# ESP_SCHEMATIC.net
KiCad netlist of a schematic drawn in Altium Designer
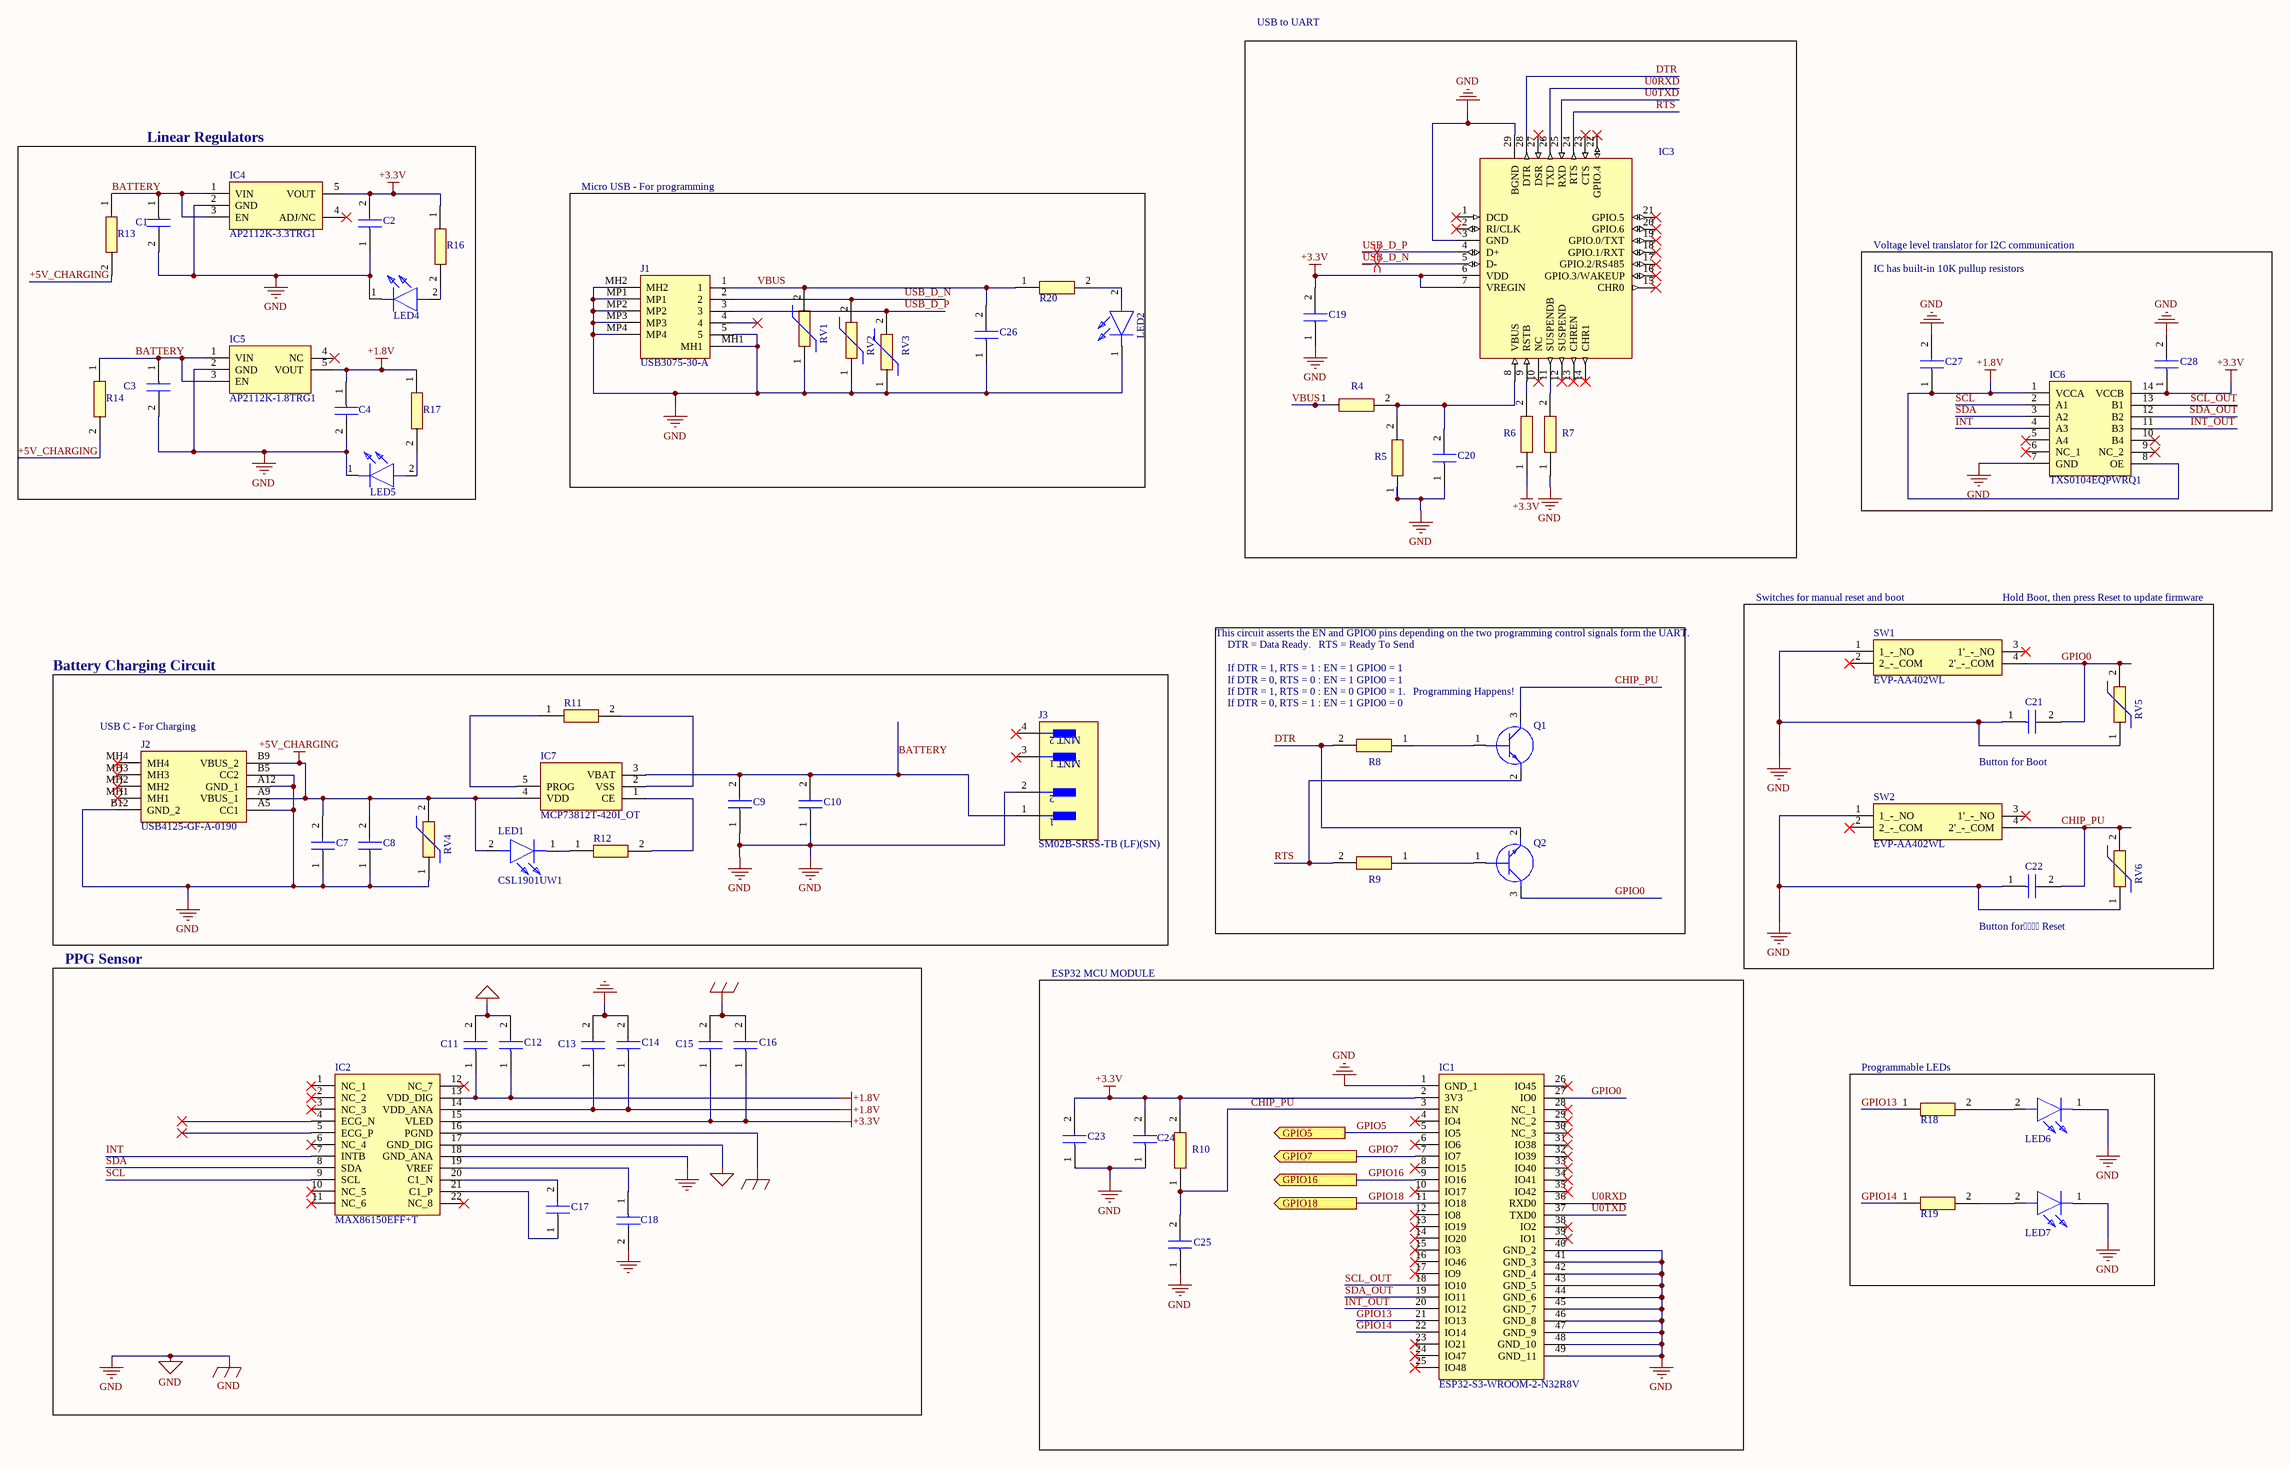
[diagram p0: ESP_SCHEMATIC.SchDoc]

(export (version "E")
  (design (tool "Eeschema 10.0.6"))
  (components
    (comp (ref "C1")
      (value "CGA3E1X7R1C105K080AC")
      (footprint "SamacSys:CAPC1608X90N")
      (description "Capacitor")
      (fields (field (name "MOUSER PART NUMBER") "810-CGA3E1X7R1C105AC"))
      (libsource (lib "*") (part "CGA3E1X7R1C105K080AC"))
    )
    (comp (ref "C2")
      (value "GRM188R71A225KE15J")
      (footprint "SamacSys:CAPC1608X90N")
      (description "Capacitor")
      (fields (field (name "MOUSER PART NUMBER") "81-GRM188R71A225KE5J"))
      (libsource (lib "*") (part "GRM188R71A225KE15J"))
    )
    (comp (ref "C3")
      (value "CGA3E1X7R1C105K080AC")
      (footprint "SamacSys:CAPC1608X90N")
      (description "Capacitor")
      (fields (field (name "MOUSER PART NUMBER") "810-CGA3E1X7R1C105AC"))
      (libsource (lib "*") (part "CGA3E1X7R1C105K080AC"))
    )
    (comp (ref "C4")
      (value "CGA3E1X7R1C105K080AC")
      (footprint "SamacSys:CAPC1608X90N")
      (description "Capacitor")
      (fields (field (name "MOUSER PART NUMBER") "810-CGA3E1X7R1C105AC"))
      (libsource (lib "*") (part "CGA3E1X7R1C105K080AC"))
    )
    (comp (ref "C7")
      (value "C0603C104K8RAC")
      (footprint "SamacSys:CAPC1608X95N")
      (description "Capacitor")
      (fields (field (name "MOUSER PART NUMBER") "80-C0603C104K8RAC"))
      (libsource (lib "*") (part "C0603C104K8RAC"))
    )
    (comp (ref "C8")
      (value "GRM188R61E106KA73J")
      (footprint "SamacSys:CAPC1608X90N")
      (description "Capacitor")
      (fields (field (name "MOUSER PART NUMBER") "81-GRM188R61E106KA3J"))
      (libsource (lib "*") (part "GRM188R61E106KA73J"))
    )
    (comp (ref "C9")
      (value "C0603C104K8RAC")
      (footprint "SamacSys:CAPC1608X95N")
      (description "Capacitor")
      (fields (field (name "MOUSER PART NUMBER") "80-C0603C104K8RAC"))
      (libsource (lib "*") (part "C0603C104K8RAC"))
    )
    (comp (ref "C10")
      (value "GRM188R61E106KA73J")
      (footprint "SamacSys:CAPC1608X90N")
      (description "Capacitor")
      (fields (field (name "MOUSER PART NUMBER") "81-GRM188R61E106KA3J"))
      (libsource (lib "*") (part "GRM188R61E106KA73J"))
    )
    (comp (ref "C11")
      (value "C1608X5R1E475K080AC")
      (footprint "SamacSys:CAPC1608X80N")
      (description "Capacitor")
      (fields (field (name "MOUSER PART NUMBER") "810-C1608X5R1E475K"))
      (libsource (lib "*") (part "C1608X5R1E475K080AC"))
    )
    (comp (ref "C12")
      (value "C0603C104K8RAC")
      (footprint "SamacSys:CAPC1608X95N")
      (description "Capacitor")
      (fields (field (name "MOUSER PART NUMBER") "80-C0603C104K8RAC"))
      (libsource (lib "*") (part "C0603C104K8RAC"))
    )
    (comp (ref "C13")
      (value "C1608X5R1E475K080AC")
      (footprint "SamacSys:CAPC1608X80N")
      (description "Capacitor")
      (fields (field (name "MOUSER PART NUMBER") "810-C1608X5R1E475K"))
      (libsource (lib "*") (part "C1608X5R1E475K080AC"))
    )
    (comp (ref "C14")
      (value "C0603C104K8RAC")
      (footprint "SamacSys:CAPC1608X95N")
      (description "Capacitor")
      (fields (field (name "MOUSER PART NUMBER") "80-C0603C104K8RAC"))
      (libsource (lib "*") (part "C0603C104K8RAC"))
    )
    (comp (ref "C15")
      (value "GRM188R61E106KA73J")
      (footprint "SamacSys:CAPC1608X90N")
      (description "Capacitor")
      (fields (field (name "MOUSER PART NUMBER") "81-GRM188R61E106KA3J"))
      (libsource (lib "*") (part "GRM188R61E106KA73J"))
    )
    (comp (ref "C16")
      (value "C0603C104K8RAC")
      (footprint "SamacSys:CAPC1608X95N")
      (description "Capacitor")
      (fields (field (name "MOUSER PART NUMBER") "80-C0603C104K8RAC"))
      (libsource (lib "*") (part "C0603C104K8RAC"))
    )
    (comp (ref "C17")
      (value "CGA3E1X7R1C105K080AC")
      (footprint "SamacSys:CAPC1608X90N")
      (description "Capacitor")
      (fields (field (name "MOUSER PART NUMBER") "810-CGA3E1X7R1C105AC"))
      (libsource (lib "*") (part "CGA3E1X7R1C105K080AC"))
    )
    (comp (ref "C18")
      (value "CGA3E1X7R1C105K080AC")
      (footprint "SamacSys:CAPC1608X90N")
      (description "Capacitor")
      (fields (field (name "MOUSER PART NUMBER") "810-CGA3E1X7R1C105AC"))
      (libsource (lib "*") (part "CGA3E1X7R1C105K080AC"))
    )
    (comp (ref "C19")
      (value "GRM188R61E106MA73J")
      (footprint "SamacSys:CAPC1608X90N")
      (description "Capacitor")
      (fields (field (name "MOUSER PART NUMBER") "81-GRM188R61E106MA3J"))
      (libsource (lib "*") (part "GRM188R61E106MA73J"))
    )
    (comp (ref "C20")
      (value "GRT188R61C105KE13D")
      (footprint "SamacSys:CAPC1608X90N")
      (description "Capacitor")
      (fields (field (name "MOUSER PART NUMBER") "81-GRT188R61C105KE3D"))
      (libsource (lib "*") (part "GRT188R61C105KE13D"))
    )
    (comp (ref "C21")
      (value "C0603C104K5RAC3121")
      (footprint "SamacSys:CAPC1608X95N")
      (description "Capacitor")
      (fields (field (name "MOUSER PART NUMBER") "80-C603C104K5RAC3121"))
      (libsource (lib "*") (part "C0603C104K5RAC3121"))
    )
    (comp (ref "C22")
      (value "C0603C104K5RAC3121")
      (footprint "SamacSys:CAPC1608X95N")
      (description "Capacitor")
      (fields (field (name "MOUSER PART NUMBER") "80-C603C104K5RAC3121"))
      (libsource (lib "*") (part "C0603C104K5RAC3121"))
    )
    (comp (ref "C23")
      (value "C0603C104K8RAC")
      (footprint "SamacSys:CAPC1608X95N")
      (description "Capacitor")
      (fields (field (name "MOUSER PART NUMBER") "80-C0603C104K8RAC"))
      (libsource (lib "*") (part "C0603C104K8RAC"))
    )
    (comp (ref "C24")
      (value "GRM188R61E106KA73J")
      (footprint "SamacSys:CAPC1608X90N")
      (description "Capacitor")
      (fields (field (name "MOUSER PART NUMBER") "81-GRM188R61E106KA3J"))
      (libsource (lib "*") (part "GRM188R61E106KA73J"))
    )
    (comp (ref "C25")
      (value "C0603C105K4RACTU")
      (footprint "SamacSys:C0603")
      (description "Capacitor")
      (fields (field (name "MOUSER PART NUMBER") "80-C0603C105K4R"))
      (libsource (lib "*") (part "C0603C105K4RACTU"))
    )
    (comp (ref "C26")
      (value "GRM188R61E106MA73J")
      (footprint "SamacSys:CAPC1608X90N")
      (description "Capacitor")
      (fields (field (name "MOUSER PART NUMBER") "81-GRM188R61E106MA3J"))
      (libsource (lib "*") (part "GRM188R61E106MA73J"))
    )
    (comp (ref "C27")
      (value "C0603C104K8RAC")
      (footprint "SamacSys:CAPC1608X95N")
      (description "Capacitor")
      (fields (field (name "MOUSER PART NUMBER") "80-C0603C104K8RAC"))
      (libsource (lib "*") (part "C0603C104K8RAC"))
    )
    (comp (ref "C28")
      (value "C0603C104K8RAC")
      (footprint "SamacSys:CAPC1608X95N")
      (description "Capacitor")
      (fields (field (name "MOUSER PART NUMBER") "80-C0603C104K8RAC"))
      (libsource (lib "*") (part "C0603C104K8RAC"))
    )
    (comp (ref "IC1")
      (value "ESP32-S3-WROOM-2-N32R8V")
      (footprint "SamacSys:ESP32S3WROOM2N32R8V")
      (description "Integrated Circuit")
      (fields (field (name "MOUSER PART NUMBER") "356-ESP3S3WRM2N32R8V"))
      (libsource (lib "*") (part "ESP32-S3-WROOM-2-N32R8V"))
    )
    (comp (ref "IC2")
      (value "MAX86150EFF+T")
      (footprint "SamacSys:MAX86150EFFT")
      (description "Integrated Circuit")
      (fields (field (name "MOUSER PART NUMBER") "700-MAX86150EFF+T"))
      (libsource (lib "SamacSys") (part "MAX86150EFF+T"))
    )
    (comp (ref "IC3")
      (value "CP2102N-A02-GQFN28")
      (footprint "SamacSys:QFN50P500X500X80-29N-D")
      (description "Integrated Circuit")
      (fields (field (name "MOUSER PART NUMBER") "634-CP2102NA02GQFN28"))
      (libsource (lib "*") (part "CP2102N-A02-GQFN28"))
    )
    (comp (ref "IC4")
      (value "AP2112K-3.3TRG1")
      (footprint "SamacSys:SOT95P282X130-5N")
      (description "Integrated Circuit")
      (fields (field (name "MOUSER PART NUMBER") "621-AP2112K-3.3TRG1"))
      (libsource (lib "*") (part "AP2112K-3.3TRG1"))
    )
    (comp (ref "IC5")
      (value "AP2112K-1.8TRG1")
      (footprint "SamacSys:SOT95P285X140-5N")
      (description "Integrated Circuit")
      (fields (field (name "MOUSER PART NUMBER") "621-AP2112K-1.8TRG1"))
      (libsource (lib "*") (part "AP2112K-1.8TRG1"))
    )
    (comp (ref "IC6")
      (value "TXS0104EQPWRQ1")
      (footprint "SamacSys:SOP65P640X120-14N")
      (description "Integrated Circuit")
      (fields (field (name "MOUSER PART NUMBER") "595-TXS0104EQPWRQ1"))
      (libsource (lib "*") (part "TXS0104EQPWRQ1"))
    )
    (comp (ref "IC7")
      (value "MCP73812T-420I_OT")
      (footprint "SamacSys:SOT95P270X145-5N")
      (description "Integrated Circuit")
      (fields
        (field (name "MANUFACTURER_PART_NUMBER") "MCP73812T-420I/OT")
        (field (name "MOUSER PART NUMBER") "579-MCP73812T-420IOT")
      )
      (libsource (lib "*") (part "MCP73812T-420I_OT"))
    )
    (comp (ref "J1")
      (value "USB3075-30-A")
      (footprint "SamacSys:USB307530A")
      (description "Connector")
      (fields (field (name "MOUSER PART NUMBER") "640-USB3075-30-A"))
      (libsource (lib "*") (part "USB3075-30-A"))
    )
    (comp (ref "J2")
      (value "USB4125-GF-A-0190")
      (footprint "SamacSys:USB4125GFA0190")
      (description "Connector")
      (fields (field (name "MOUSER PART NUMBER") "640-USB4125-GF-A-190"))
      (libsource (lib "*") (part "USB4125-GF-A-0190"))
    )
    (comp (ref "J3")
      (value "SM02B-SRSS-TB (LF)(SN)")
      (footprint "FP-SM02B-SRSS-TB_LF_SN-MFG")
      (description "CONN HEADER SMD R/A 2POS 1MM")
      (libsource (lib "Altium Content Vault") (part "029478cb6d4f2fad0cd2a245525ee6d"))
    )
    (comp (ref "LED1")
      (value "CSL1901UW1")
      (footprint "SamacSys:CSL1901UW1")
      (description "LED")
      (fields (field (name "MOUSER PART NUMBER") "755-CSL1901UW1"))
      (libsource (lib "*") (part "CSL1901UW1"))
    )
    (comp (ref "LED2")
      (value "SMLD12BN1WT86")
      (footprint "SamacSys:LEDM168X65N")
      (description "LED")
      (fields (field (name "MOUSER PART NUMBER") "755-SMLD12BN1WT86"))
      (libsource (lib "*") (part "SMLD12BN1WT86"))
    )
    (comp (ref "LED4")
      (value "CSL1901YW1")
      (footprint "SamacSys:CSL1901YW1")
      (description "LED")
      (fields (field (name "MOUSER PART NUMBER") "755-CSL1901YW1"))
      (libsource (lib "*") (part "CSL1901YW1"))
    )
    (comp (ref "LED5")
      (value "CSL1901YW1")
      (footprint "SamacSys:CSL1901YW1")
      (description "LED")
      (fields (field (name "MOUSER PART NUMBER") "755-CSL1901YW1"))
      (libsource (lib "*") (part "CSL1901YW1"))
    )
    (comp (ref "LED6")
      (value "CSL1901YW1")
      (footprint "SamacSys:CSL1901YW1")
      (description "LED")
      (fields (field (name "MOUSER PART NUMBER") "755-CSL1901YW1"))
      (libsource (lib "*") (part "CSL1901YW1"))
    )
    (comp (ref "LED7")
      (value "CSL1901YW1")
      (footprint "SamacSys:CSL1901YW1")
      (description "LED")
      (fields (field (name "MOUSER PART NUMBER") "755-CSL1901YW1"))
      (libsource (lib "*") (part "CSL1901YW1"))
    )
    (comp (ref "Q1")
      (value "KSC3265YMTF")
      (footprint "SamacSys:SOT96P237X111-3N")
      (description "Transistor BJT NPN")
      (fields (field (name "MOUSER PART NUMBER") "512-KSC3265YMTF"))
      (libsource (lib "*") (part "KSC3265YMTF"))
    )
    (comp (ref "Q2")
      (value "KSC3265YMTF")
      (footprint "SamacSys:SOT96P237X111-3N")
      (description "Transistor BJT NPN")
      (fields (field (name "MOUSER PART NUMBER") "512-KSC3265YMTF"))
      (libsource (lib "*") (part "KSC3265YMTF"))
    )
    (comp (ref "R4")
      (value "ERJUP3F2212V")
      (footprint "SamacSys:ERJUP3")
      (description "Resistor")
      (libsource (lib "*") (part "ERJUP3F2212V"))
    )
    (comp (ref "R5")
      (value "ERJUP3F4752V")
      (footprint "SamacSys:ERJUP3")
      (description "Resistor")
      (libsource (lib "*") (part "ERJUP3F4752V"))
    )
    (comp (ref "R6")
      (value "ERJUP3F1001V")
      (footprint "SamacSys:ERJUP3")
      (description "Resistor")
      (libsource (lib "") (part "ERJUP3F1001V_1"))
    )
    (comp (ref "R7")
      (value "ERJ-UP3J103V")
      (footprint "SamacSys:ERJUP3")
      (description "Resistor")
      (fields (field (name "MOUSER PART NUMBER") "667-ERJ-UP3J103V"))
      (libsource (lib "*") (part "ERJ-UP3J103V"))
    )
    (comp (ref "R8")
      (value "ERJ-UP3J103V")
      (footprint "SamacSys:ERJUP3")
      (description "Resistor")
      (fields (field (name "MOUSER PART NUMBER") "667-ERJ-UP3J103V"))
      (libsource (lib "") (part "ERJ-UP3J103V_1"))
    )
    (comp (ref "R9")
      (value "ERJ-UP3J103V")
      (footprint "SamacSys:ERJUP3")
      (description "Resistor")
      (fields (field (name "MOUSER PART NUMBER") "667-ERJ-UP3J103V"))
      (libsource (lib "") (part "ERJ-UP3J103V_1"))
    )
    (comp (ref "R10")
      (value "ERJ-UP3J103V")
      (footprint "SamacSys:ERJUP3")
      (description "Resistor")
      (fields (field (name "MOUSER PART NUMBER") "667-ERJ-UP3J103V"))
      (libsource (lib "*") (part "ERJ-UP3J103V"))
    )
    (comp (ref "R11")
      (value "ERJUP3F2001V")
      (footprint "SamacSys:ERJUP3")
      (description "Resistor")
      (libsource (lib "*") (part "ERJUP3F2001V"))
    )
    (comp (ref "R12")
      (value "ERJUP3F1001V")
      (footprint "SamacSys:ERJUP3")
      (description "Resistor")
      (libsource (lib "*") (part "ERJUP3F1001V"))
    )
    (comp (ref "R13")
      (value "ERA-3AEB101V")
      (footprint "SamacSys:ERA3AEB101V")
      (description "Resistor")
      (fields (field (name "MOUSER PART NUMBER") "667-ERA-3AEB101V"))
      (libsource (lib "*") (part "ERA-3AEB101V"))
    )
    (comp (ref "R14")
      (value "ERA-3AEB101V")
      (footprint "SamacSys:ERA3AEB101V")
      (description "Resistor")
      (fields (field (name "MOUSER PART NUMBER") "667-ERA-3AEB101V"))
      (libsource (lib "*") (part "ERA-3AEB101V"))
    )
    (comp (ref "R16")
      (value "RT0603BRE075KL")
      (footprint "SamacSys:RESC1608X55N")
      (description "Resistor")
      (fields (field (name "MOUSER PART NUMBER") "603-RT0603BRE075KL"))
      (libsource (lib "") (part "RT0603BRE075KL_1"))
    )
    (comp (ref "R17")
      (value "RT0603BRE075KL")
      (footprint "SamacSys:RESC1608X55N")
      (description "Resistor")
      (fields (field (name "MOUSER PART NUMBER") "603-RT0603BRE075KL"))
      (libsource (lib "") (part "RT0603BRE075KL_1"))
    )
    (comp (ref "R18")
      (value "RT0603BRE075KL")
      (footprint "SamacSys:RESC1608X55N")
      (description "Resistor")
      (fields (field (name "MOUSER PART NUMBER") "603-RT0603BRE075KL"))
      (libsource (lib "*") (part "RT0603BRE075KL"))
    )
    (comp (ref "R19")
      (value "RT0603BRE075KL")
      (footprint "SamacSys:RESC1608X55N")
      (description "Resistor")
      (fields (field (name "MOUSER PART NUMBER") "603-RT0603BRE075KL"))
      (libsource (lib "*") (part "RT0603BRE075KL"))
    )
    (comp (ref "R20")
      (value "RT0603BRE075KL")
      (footprint "SamacSys:RESC1608X55N")
      (description "Resistor")
      (fields (field (name "MOUSER PART NUMBER") "603-RT0603BRE075KL"))
      (libsource (lib "*") (part "RT0603BRE075KL"))
    )
    (comp (ref "RV1")
      (value "CG0603MLC-05E")
      (footprint "SamacSys:VARC1608X55N")
      (description "Varistor")
      (fields (field (name "MOUSER PART NUMBER") "652-CG0603MLC-05E"))
      (libsource (lib "*") (part "CG0603MLC-05E"))
    )
    (comp (ref "RV2")
      (value "CG0603MLC-05E")
      (footprint "SamacSys:VARC1608X55N")
      (description "Varistor")
      (fields (field (name "MOUSER PART NUMBER") "652-CG0603MLC-05E"))
      (libsource (lib "*") (part "CG0603MLC-05E"))
    )
    (comp (ref "RV3")
      (value "CG0603MLC-05E")
      (footprint "SamacSys:VARC1608X55N")
      (description "Varistor")
      (fields (field (name "MOUSER PART NUMBER") "652-CG0603MLC-05E"))
      (libsource (lib "*") (part "CG0603MLC-05E"))
    )
    (comp (ref "RV4")
      (value "CG0603MLC-05E")
      (footprint "SamacSys:VARC1608X55N")
      (description "Varistor")
      (fields (field (name "MOUSER PART NUMBER") "652-CG0603MLC-05E"))
      (libsource (lib "*") (part "CG0603MLC-05E"))
    )
    (comp (ref "RV5")
      (value "CG0603MLC-05E")
      (footprint "SamacSys:VARC1608X55N")
      (description "Varistor")
      (fields (field (name "MOUSER PART NUMBER") "652-CG0603MLC-05E"))
      (libsource (lib "*") (part "CG0603MLC-05E"))
    )
    (comp (ref "RV6")
      (value "CG0603MLC-05E")
      (footprint "SamacSys:VARC1608X55N")
      (description "Varistor")
      (fields (field (name "MOUSER PART NUMBER") "652-CG0603MLC-05E"))
      (libsource (lib "*") (part "CG0603MLC-05E"))
    )
    (comp (ref "SW1")
      (value "EVP-AA402WL")
      (footprint "SamacSys:EVPAA")
      (description "Switch")
      (libsource (lib "*") (part "EVP-AA402WL"))
    )
    (comp (ref "SW2")
      (value "EVP-AA402WL")
      (footprint "SamacSys:EVPAA")
      (description "Switch")
      (libsource (lib "*") (part "EVP-AA402WL"))
    )
  )
  (nets
    (net (code "1") (name "+1.8V") (class "Default")
      (node (ref "C11") (pin "1") (pinfunction "1_1") (pintype "passive"))
      (node (ref "C12") (pin "1") (pinfunction "1_1") (pintype "passive"))
      (node (ref "C13") (pin "1") (pinfunction "1_1") (pintype "passive"))
      (node (ref "C14") (pin "1") (pinfunction "1_1") (pintype "passive"))
      (node (ref "C27") (pin "1") (pinfunction "1_1") (pintype "passive"))
      (node (ref "C4") (pin "1") (pinfunction "1_1") (pintype "passive"))
      (node (ref "IC2") (pin "13") (pinfunction "VDD_DIG_13") (pintype "passive"))
      (node (ref "IC2") (pin "14") (pinfunction "VDD_ANA_14") (pintype "passive"))
      (node (ref "IC5") (pin "5") (pinfunction "VOUT_5") (pintype "passive"))
      (node (ref "IC6") (pin "1") (pinfunction "VCCA_1") (pintype "passive"))
      (node (ref "IC6") (pin "8") (pinfunction "OE_8") (pintype "passive"))
      (node (ref "R17") (pin "1") (pinfunction "1_1") (pintype "passive"))
    )
    (net (code "2") (name "+3.3V") (class "Default")
      (node (ref "C15") (pin "1") (pinfunction "1_1") (pintype "passive"))
      (node (ref "C16") (pin "1") (pinfunction "1_1") (pintype "passive"))
      (node (ref "C19") (pin "2") (pinfunction "2_2") (pintype "passive"))
      (node (ref "C2") (pin "2") (pinfunction "2_2") (pintype "passive"))
      (node (ref "C23") (pin "2") (pinfunction "2_2") (pintype "passive"))
      (node (ref "C24") (pin "2") (pinfunction "2_2") (pintype "passive"))
      (node (ref "C28") (pin "1") (pinfunction "1_1") (pintype "passive"))
      (node (ref "IC1") (pin "2") (pinfunction "3V3_2") (pintype "passive"))
      (node (ref "IC2") (pin "15") (pinfunction "VLED_15") (pintype "passive"))
      (node (ref "IC3") (pin "6") (pinfunction "VDD_6") (pintype "power_in"))
      (node (ref "IC3") (pin "7") (pinfunction "VREGIN_7") (pintype "power_in"))
      (node (ref "IC4") (pin "5") (pinfunction "VOUT_5") (pintype "passive"))
      (node (ref "IC6") (pin "14") (pinfunction "VCCB_14") (pintype "passive"))
      (node (ref "R10") (pin "2") (pinfunction "2_2") (pintype "passive"))
      (node (ref "R16") (pin "1") (pinfunction "1_1") (pintype "passive"))
      (node (ref "R6") (pin "1") (pinfunction "1_1") (pintype "passive"))
    )
    (net (code "3") (name "+5V_CHARGING") (class "Default")
      (node (ref "C7") (pin "2") (pinfunction "2_2") (pintype "passive"))
      (node (ref "C8") (pin "2") (pinfunction "2_2") (pintype "passive"))
      (node (ref "IC7") (pin "4") (pinfunction "VDD_4") (pintype "passive"))
      (node (ref "J2") (pin "A9") (pinfunction "VBUS_1_A9") (pintype "passive"))
      (node (ref "J2") (pin "B9") (pinfunction "VBUS_2_B9") (pintype "passive"))
      (node (ref "LED1") (pin "2") (pinfunction "A_2") (pintype "passive"))
      (node (ref "R13") (pin "2") (pinfunction "2_2") (pintype "passive"))
      (node (ref "R14") (pin "2") (pinfunction "2_2") (pintype "passive"))
      (node (ref "RV4") (pin "2") (pinfunction "2_2") (pintype "passive"))
    )
    (net (code "4") (name "/BATTERY") (class "Default")
      (node (ref "C1") (pin "1") (pinfunction "1_1") (pintype "passive"))
      (node (ref "C10") (pin "2") (pinfunction "2_2") (pintype "passive"))
      (node (ref "C3") (pin "1") (pinfunction "1_1") (pintype "passive"))
      (node (ref "C9") (pin "2") (pinfunction "2_2") (pintype "passive"))
      (node (ref "IC4") (pin "1") (pinfunction "VIN_1") (pintype "passive"))
      (node (ref "IC4") (pin "3") (pinfunction "EN_3") (pintype "passive"))
      (node (ref "IC5") (pin "1") (pinfunction "VIN_1") (pintype "passive"))
      (node (ref "IC5") (pin "3") (pinfunction "EN_3") (pintype "passive"))
      (node (ref "IC7") (pin "3") (pinfunction "VBAT_3") (pintype "passive"))
      (node (ref "J3") (pin "1") (pinfunction "1_1") (pintype "passive"))
      (node (ref "R13") (pin "1") (pinfunction "1_1") (pintype "passive"))
      (node (ref "R14") (pin "1") (pinfunction "1_1") (pintype "passive"))
    )
    (net (code "5") (name "/CHIP_PU") (class "Default")
      (node (ref "C22") (pin "2") (pinfunction "2_2") (pintype "passive"))
      (node (ref "C25") (pin "2") (pinfunction "2_2") (pintype "passive"))
      (node (ref "IC1") (pin "3") (pinfunction "EN_3") (pintype "passive"))
      (node (ref "Q1") (pin "3") (pinfunction "C_3") (pintype "passive"))
      (node (ref "R10") (pin "1") (pinfunction "1_1") (pintype "passive"))
      (node (ref "RV6") (pin "2") (pinfunction "2_2") (pintype "passive"))
      (node (ref "SW2") (pin "4") (pinfunction "2'_-_COM_4") (pintype "passive"))
    )
    (net (code "6") (name "/DTR") (class "Default")
      (node (ref "IC3") (pin "28") (pinfunction "DTR_28") (pintype "output"))
      (node (ref "Q2") (pin "2") (pinfunction "E_2") (pintype "passive"))
      (node (ref "R8") (pin "2") (pinfunction "2_2") (pintype "passive"))
    )
    (net (code "7") (name "/GPIO0") (class "Default")
      (node (ref "C21") (pin "2") (pinfunction "2_2") (pintype "passive"))
      (node (ref "IC1") (pin "27") (pinfunction "IO0_27") (pintype "passive"))
      (node (ref "Q2") (pin "3") (pinfunction "C_3") (pintype "passive"))
      (node (ref "RV5") (pin "2") (pinfunction "2_2") (pintype "passive"))
      (node (ref "SW1") (pin "4") (pinfunction "2'_-_COM_4") (pintype "passive"))
    )
    (net (code "8") (name "/GPIO5") (class "Default")
      (node (ref "IC1") (pin "5") (pinfunction "IO5_5") (pintype "passive"))
    )
    (net (code "9") (name "/GPIO7") (class "Default")
      (node (ref "IC1") (pin "7") (pinfunction "IO7_7") (pintype "passive"))
    )
    (net (code "10") (name "/GPIO13") (class "Default")
      (node (ref "IC1") (pin "21") (pinfunction "IO13_21") (pintype "passive"))
      (node (ref "R18") (pin "1") (pinfunction "1_1") (pintype "passive"))
    )
    (net (code "11") (name "/GPIO14") (class "Default")
      (node (ref "IC1") (pin "22") (pinfunction "IO14_22") (pintype "passive"))
      (node (ref "R19") (pin "1") (pinfunction "1_1") (pintype "passive"))
    )
    (net (code "12") (name "/GPIO16") (class "Default")
      (node (ref "IC1") (pin "9") (pinfunction "IO16_9") (pintype "passive"))
    )
    (net (code "13") (name "/GPIO18") (class "Default")
      (node (ref "IC1") (pin "11") (pinfunction "IO18_11") (pintype "passive"))
    )
    (net (code "14") (name "/INT") (class "Default")
      (node (ref "IC2") (pin "7") (pinfunction "INTB_7") (pintype "passive"))
      (node (ref "IC6") (pin "4") (pinfunction "A3_4") (pintype "passive"))
    )
    (net (code "15") (name "/INT_OUT") (class "Default")
      (node (ref "IC1") (pin "20") (pinfunction "IO12_20") (pintype "passive"))
      (node (ref "IC6") (pin "11") (pinfunction "B3_11") (pintype "passive"))
    )
    (net (code "16") (name "/RTS") (class "Default")
      (node (ref "IC3") (pin "24") (pinfunction "RTS_24") (pintype "output"))
      (node (ref "Q1") (pin "2") (pinfunction "E_2") (pintype "passive"))
      (node (ref "R9") (pin "2") (pinfunction "2_2") (pintype "passive"))
    )
    (net (code "17") (name "/SCL") (class "Default")
      (node (ref "IC2") (pin "9") (pinfunction "SCL_9") (pintype "passive"))
      (node (ref "IC6") (pin "2") (pinfunction "A1_2") (pintype "passive"))
    )
    (net (code "18") (name "/SCL_OUT") (class "Default")
      (node (ref "IC1") (pin "18") (pinfunction "IO10_18") (pintype "passive"))
      (node (ref "IC6") (pin "13") (pinfunction "B1_13") (pintype "passive"))
    )
    (net (code "19") (name "/SDA") (class "Default")
      (node (ref "IC2") (pin "8") (pinfunction "SDA_8") (pintype "passive"))
      (node (ref "IC6") (pin "3") (pinfunction "A2_3") (pintype "passive"))
    )
    (net (code "20") (name "/SDA_OUT") (class "Default")
      (node (ref "IC1") (pin "19") (pinfunction "IO11_19") (pintype "passive"))
      (node (ref "IC6") (pin "12") (pinfunction "B2_12") (pintype "passive"))
    )
    (net (code "21") (name "/U0RXD") (class "Default")
      (node (ref "IC1") (pin "36") (pinfunction "RXD0_36") (pintype "passive"))
      (node (ref "IC3") (pin "26") (pinfunction "TXD_26") (pintype "output"))
    )
    (net (code "22") (name "/U0TXD") (class "Default")
      (node (ref "IC1") (pin "37") (pinfunction "TXD0_37") (pintype "passive"))
      (node (ref "IC3") (pin "25") (pinfunction "RXD_25") (pintype "input"))
    )
    (net (code "23") (name "/USB_D_N") (class "Default")
      (node (ref "IC3") (pin "5") (pinfunction "D-_5") (pintype "bidirectional"))
      (node (ref "J1") (pin "2") (pinfunction "2_2") (pintype "passive"))
      (node (ref "RV2") (pin "2") (pinfunction "2_2") (pintype "passive"))
    )
    (net (code "24") (name "/USB_D_P") (class "Default")
      (node (ref "IC3") (pin "4") (pinfunction "D+_4") (pintype "bidirectional"))
      (node (ref "J1") (pin "3") (pinfunction "3_3") (pintype "passive"))
      (node (ref "RV3") (pin "2") (pinfunction "2_2") (pintype "passive"))
    )
    (net (code "25") (name "/VBUS") (class "Default")
      (node (ref "C26") (pin "2") (pinfunction "2_2") (pintype "passive"))
      (node (ref "J1") (pin "1") (pinfunction "1_1") (pintype "passive"))
      (node (ref "R20") (pin "1") (pinfunction "1_1") (pintype "passive"))
      (node (ref "R4") (pin "1") (pinfunction "1_1") (pintype "passive"))
      (node (ref "RV1") (pin "2") (pinfunction "2_2") (pintype "passive"))
    )
    (net (code "26") (name "GND") (class "Default")
      (node (ref "C1") (pin "2") (pinfunction "2_2") (pintype "passive"))
      (node (ref "C10") (pin "1") (pinfunction "1_1") (pintype "passive"))
      (node (ref "C11") (pin "2") (pinfunction "2_2") (pintype "passive"))
      (node (ref "C12") (pin "2") (pinfunction "2_2") (pintype "passive"))
      (node (ref "C13") (pin "2") (pinfunction "2_2") (pintype "passive"))
      (node (ref "C14") (pin "2") (pinfunction "2_2") (pintype "passive"))
      (node (ref "C15") (pin "2") (pinfunction "2_2") (pintype "passive"))
      (node (ref "C16") (pin "2") (pinfunction "2_2") (pintype "passive"))
      (node (ref "C18") (pin "2") (pinfunction "2_2") (pintype "passive"))
      (node (ref "C19") (pin "1") (pinfunction "1_1") (pintype "passive"))
      (node (ref "C2") (pin "1") (pinfunction "1_1") (pintype "passive"))
      (node (ref "C20") (pin "1") (pinfunction "1_1") (pintype "passive"))
      (node (ref "C21") (pin "1") (pinfunction "1_1") (pintype "passive"))
      (node (ref "C22") (pin "1") (pinfunction "1_1") (pintype "passive"))
      (node (ref "C23") (pin "1") (pinfunction "1_1") (pintype "passive"))
      (node (ref "C24") (pin "1") (pinfunction "1_1") (pintype "passive"))
      (node (ref "C25") (pin "1") (pinfunction "1_1") (pintype "passive"))
      (node (ref "C26") (pin "1") (pinfunction "1_1") (pintype "passive"))
      (node (ref "C27") (pin "2") (pinfunction "2_2") (pintype "passive"))
      (node (ref "C28") (pin "2") (pinfunction "2_2") (pintype "passive"))
      (node (ref "C3") (pin "2") (pinfunction "2_2") (pintype "passive"))
      (node (ref "C4") (pin "2") (pinfunction "2_2") (pintype "passive"))
      (node (ref "C7") (pin "1") (pinfunction "1_1") (pintype "passive"))
      (node (ref "C8") (pin "1") (pinfunction "1_1") (pintype "passive"))
      (node (ref "C9") (pin "1") (pinfunction "1_1") (pintype "passive"))
      (node (ref "IC1") (pin "1") (pinfunction "GND_1_1") (pintype "passive"))
      (node (ref "IC1") (pin "40") (pinfunction "GND_2_40") (pintype "passive"))
      (node (ref "IC1") (pin "41") (pinfunction "GND_3_41") (pintype "passive"))
      (node (ref "IC1") (pin "42") (pinfunction "GND_4_42") (pintype "passive"))
      (node (ref "IC1") (pin "43") (pinfunction "GND_5_43") (pintype "passive"))
      (node (ref "IC1") (pin "44") (pinfunction "GND_6_44") (pintype "passive"))
      (node (ref "IC1") (pin "45") (pinfunction "GND_7_45") (pintype "passive"))
      (node (ref "IC1") (pin "46") (pinfunction "GND_8_46") (pintype "passive"))
      (node (ref "IC1") (pin "47") (pinfunction "GND_9_47") (pintype "passive"))
      (node (ref "IC1") (pin "48") (pinfunction "GND_10_48") (pintype "passive"))
      (node (ref "IC1") (pin "49") (pinfunction "GND_11_49") (pintype "passive"))
      (node (ref "IC2") (pin "16") (pinfunction "PGND_16") (pintype "passive"))
      (node (ref "IC2") (pin "17") (pinfunction "GND_DIG_17") (pintype "passive"))
      (node (ref "IC2") (pin "18") (pinfunction "GND_ANA_18") (pintype "passive"))
      (node (ref "IC3") (pin "29") (pinfunction "BGND_29") (pintype "power_in"))
      (node (ref "IC3") (pin "3") (pinfunction "GND_3") (pintype "power_in"))
      (node (ref "IC4") (pin "2") (pinfunction "GND_2") (pintype "passive"))
      (node (ref "IC5") (pin "2") (pinfunction "GND_2") (pintype "passive"))
      (node (ref "IC6") (pin "7") (pinfunction "GND_7") (pintype "passive"))
      (node (ref "J1") (pin "5") (pinfunction "5_5") (pintype "passive"))
      (node (ref "J1") (pin "MH1") (pinfunction "MH1_MH1") (pintype "passive"))
      (node (ref "J1") (pin "MH2") (pinfunction "MH2_MH2") (pintype "passive"))
      (node (ref "J1") (pin "MP1") (pinfunction "MP1_MP1") (pintype "passive"))
      (node (ref "J1") (pin "MP2") (pinfunction "MP2_MP2") (pintype "passive"))
      (node (ref "J1") (pin "MP3") (pinfunction "MP3_MP3") (pintype "passive"))
      (node (ref "J1") (pin "MP4") (pinfunction "MP4_MP4") (pintype "passive"))
      (node (ref "J2") (pin "A12") (pinfunction "GND_1_A12") (pintype "passive"))
      (node (ref "J2") (pin "A5") (pinfunction "CC1_A5") (pintype "passive"))
      (node (ref "J2") (pin "B12") (pinfunction "GND_2_B12") (pintype "passive"))
      (node (ref "J2") (pin "B5") (pinfunction "CC2_B5") (pintype "passive"))
      (node (ref "J3") (pin "2") (pinfunction "2_2") (pintype "passive"))
      (node (ref "LED2") (pin "1") (pinfunction "K_1") (pintype "passive"))
      (node (ref "LED4") (pin "1") (pinfunction "K_1") (pintype "passive"))
      (node (ref "LED5") (pin "1") (pinfunction "K_1") (pintype "passive"))
      (node (ref "LED6") (pin "1") (pinfunction "K_1") (pintype "passive"))
      (node (ref "LED7") (pin "1") (pinfunction "K_1") (pintype "passive"))
      (node (ref "R5") (pin "1") (pinfunction "1_1") (pintype "passive"))
      (node (ref "R7") (pin "1") (pinfunction "1_1") (pintype "passive"))
      (node (ref "RV1") (pin "1") (pinfunction "1_1") (pintype "passive"))
      (node (ref "RV2") (pin "1") (pinfunction "1_1") (pintype "passive"))
      (node (ref "RV3") (pin "1") (pinfunction "1_1") (pintype "passive"))
      (node (ref "RV4") (pin "1") (pinfunction "1_1") (pintype "passive"))
      (node (ref "RV5") (pin "1") (pinfunction "1_1") (pintype "passive"))
      (node (ref "RV6") (pin "1") (pinfunction "1_1") (pintype "passive"))
      (node (ref "SW1") (pin "1") (pinfunction "1_-_NO_1") (pintype "passive"))
      (node (ref "SW2") (pin "1") (pinfunction "1_-_NO_1") (pintype "passive"))
    )
    (net (code "27") (name "Net-(IC2-C1_N)") (class "Default")
      (node (ref "C17") (pin "2") (pinfunction "2_2") (pintype "passive"))
      (node (ref "IC2") (pin "20") (pinfunction "C1_N_20") (pintype "passive"))
    )
    (net (code "28") (name "Net-(IC2-C1_P)") (class "Default")
      (node (ref "C17") (pin "1") (pinfunction "1_1") (pintype "passive"))
      (node (ref "IC2") (pin "21") (pinfunction "C1_P_21") (pintype "passive"))
    )
    (net (code "29") (name "Net-(IC2-VREF)") (class "Default")
      (node (ref "C18") (pin "1") (pinfunction "1_1") (pintype "passive"))
      (node (ref "IC2") (pin "19") (pinfunction "VREF_19") (pintype "passive"))
    )
    (net (code "30") (name "Net-(IC3-RSTB)") (class "Default")
      (node (ref "IC3") (pin "9") (pinfunction "RSTB_9") (pintype "input"))
      (node (ref "R6") (pin "2") (pinfunction "2_2") (pintype "passive"))
    )
    (net (code "31") (name "Net-(IC3-SUSPENDB)") (class "Default")
      (node (ref "IC3") (pin "11") (pinfunction "SUSPENDB_11") (pintype "output"))
      (node (ref "R7") (pin "2") (pinfunction "2_2") (pintype "passive"))
    )
    (net (code "32") (name "Net-(IC3-VBUS)") (class "Default")
      (node (ref "C20") (pin "2") (pinfunction "2_2") (pintype "passive"))
      (node (ref "IC3") (pin "8") (pinfunction "VBUS_8") (pintype "input"))
      (node (ref "R4") (pin "2") (pinfunction "2_2") (pintype "passive"))
      (node (ref "R5") (pin "2") (pinfunction "2_2") (pintype "passive"))
    )
    (net (code "33") (name "Net-(IC7-CE)") (class "Default")
      (node (ref "IC7") (pin "1") (pinfunction "CE_1") (pintype "passive"))
      (node (ref "R12") (pin "2") (pinfunction "2_2") (pintype "passive"))
    )
    (net (code "34") (name "Net-(IC7-PROG)") (class "Default")
      (node (ref "IC7") (pin "5") (pinfunction "PROG_5") (pintype "passive"))
      (node (ref "R11") (pin "1") (pinfunction "1_1") (pintype "passive"))
    )
    (net (code "35") (name "Net-(IC7-VSS)") (class "Default")
      (node (ref "IC7") (pin "2") (pinfunction "VSS_2") (pintype "passive"))
      (node (ref "R11") (pin "2") (pinfunction "2_2") (pintype "passive"))
    )
    (net (code "36") (name "Net-(LED1-K)") (class "Default")
      (node (ref "LED1") (pin "1") (pinfunction "K_1") (pintype "passive"))
      (node (ref "R12") (pin "1") (pinfunction "1_1") (pintype "passive"))
    )
    (net (code "37") (name "Net-(LED2-A)") (class "Default")
      (node (ref "LED2") (pin "2") (pinfunction "A_2") (pintype "passive"))
      (node (ref "R20") (pin "2") (pinfunction "2_2") (pintype "passive"))
    )
    (net (code "38") (name "Net-(LED4-A)") (class "Default")
      (node (ref "LED4") (pin "2") (pinfunction "A_2") (pintype "passive"))
      (node (ref "R16") (pin "2") (pinfunction "2_2") (pintype "passive"))
    )
    (net (code "39") (name "Net-(LED5-A)") (class "Default")
      (node (ref "LED5") (pin "2") (pinfunction "A_2") (pintype "passive"))
      (node (ref "R17") (pin "2") (pinfunction "2_2") (pintype "passive"))
    )
    (net (code "40") (name "Net-(LED6-A)") (class "Default")
      (node (ref "LED6") (pin "2") (pinfunction "A_2") (pintype "passive"))
      (node (ref "R18") (pin "2") (pinfunction "2_2") (pintype "passive"))
    )
    (net (code "41") (name "Net-(LED7-A)") (class "Default")
      (node (ref "LED7") (pin "2") (pinfunction "A_2") (pintype "passive"))
      (node (ref "R19") (pin "2") (pinfunction "2_2") (pintype "passive"))
    )
    (net (code "42") (name "Net-(Q1-B)") (class "Default")
      (node (ref "Q1") (pin "1") (pinfunction "B_1") (pintype "passive"))
      (node (ref "R8") (pin "1") (pinfunction "1_1") (pintype "passive"))
    )
    (net (code "43") (name "Net-(Q2-B)") (class "Default")
      (node (ref "Q2") (pin "1") (pinfunction "B_1") (pintype "passive"))
      (node (ref "R9") (pin "1") (pinfunction "1_1") (pintype "passive"))
    )
    (net (code "44") (name "unconnected-(IC1-IO1-Pad39)") (class "Default")
      (node (ref "IC1") (pin "39") (pinfunction "IO1_39") (pintype "passive+no_connect"))
    )
    (net (code "45") (name "unconnected-(IC1-IO2-Pad38)") (class "Default")
      (node (ref "IC1") (pin "38") (pinfunction "IO2_38") (pintype "passive+no_connect"))
    )
    (net (code "46") (name "unconnected-(IC1-IO3-Pad15)") (class "Default")
      (node (ref "IC1") (pin "15") (pinfunction "IO3_15") (pintype "passive+no_connect"))
    )
    (net (code "47") (name "unconnected-(IC1-IO4-Pad4)") (class "Default")
      (node (ref "IC1") (pin "4") (pinfunction "IO4_4") (pintype "passive+no_connect"))
    )
    (net (code "48") (name "unconnected-(IC1-IO6-Pad6)") (class "Default")
      (node (ref "IC1") (pin "6") (pinfunction "IO6_6") (pintype "passive+no_connect"))
    )
    (net (code "49") (name "unconnected-(IC1-IO8-Pad12)") (class "Default")
      (node (ref "IC1") (pin "12") (pinfunction "IO8_12") (pintype "passive+no_connect"))
    )
    (net (code "50") (name "unconnected-(IC1-IO9-Pad17)") (class "Default")
      (node (ref "IC1") (pin "17") (pinfunction "IO9_17") (pintype "passive+no_connect"))
    )
    (net (code "51") (name "unconnected-(IC1-IO15-Pad8)") (class "Default")
      (node (ref "IC1") (pin "8") (pinfunction "IO15_8") (pintype "passive+no_connect"))
    )
    (net (code "52") (name "unconnected-(IC1-IO17-Pad10)") (class "Default")
      (node (ref "IC1") (pin "10") (pinfunction "IO17_10") (pintype "passive+no_connect"))
    )
    (net (code "53") (name "unconnected-(IC1-IO19-Pad13)") (class "Default")
      (node (ref "IC1") (pin "13") (pinfunction "IO19_13") (pintype "passive+no_connect"))
    )
    (net (code "54") (name "unconnected-(IC1-IO20-Pad14)") (class "Default")
      (node (ref "IC1") (pin "14") (pinfunction "IO20_14") (pintype "passive+no_connect"))
    )
    (net (code "55") (name "unconnected-(IC1-IO21-Pad23)") (class "Default")
      (node (ref "IC1") (pin "23") (pinfunction "IO21_23") (pintype "passive+no_connect"))
    )
    (net (code "56") (name "unconnected-(IC1-IO38-Pad31)") (class "Default")
      (node (ref "IC1") (pin "31") (pinfunction "IO38_31") (pintype "passive+no_connect"))
    )
    (net (code "57") (name "unconnected-(IC1-IO39-Pad32)") (class "Default")
      (node (ref "IC1") (pin "32") (pinfunction "IO39_32") (pintype "passive+no_connect"))
    )
    (net (code "58") (name "unconnected-(IC1-IO40-Pad33)") (class "Default")
      (node (ref "IC1") (pin "33") (pinfunction "IO40_33") (pintype "passive+no_connect"))
    )
    (net (code "59") (name "unconnected-(IC1-IO41-Pad34)") (class "Default")
      (node (ref "IC1") (pin "34") (pinfunction "IO41_34") (pintype "passive+no_connect"))
    )
    (net (code "60") (name "unconnected-(IC1-IO42-Pad35)") (class "Default")
      (node (ref "IC1") (pin "35") (pinfunction "IO42_35") (pintype "passive+no_connect"))
    )
    (net (code "61") (name "unconnected-(IC1-IO45-Pad26)") (class "Default")
      (node (ref "IC1") (pin "26") (pinfunction "IO45_26") (pintype "passive+no_connect"))
    )
    (net (code "62") (name "unconnected-(IC1-IO46-Pad16)") (class "Default")
      (node (ref "IC1") (pin "16") (pinfunction "IO46_16") (pintype "passive+no_connect"))
    )
    (net (code "63") (name "unconnected-(IC1-IO47-Pad24)") (class "Default")
      (node (ref "IC1") (pin "24") (pinfunction "IO47_24") (pintype "passive+no_connect"))
    )
    (net (code "64") (name "unconnected-(IC1-IO48-Pad25)") (class "Default")
      (node (ref "IC1") (pin "25") (pinfunction "IO48_25") (pintype "passive+no_connect"))
    )
    (net (code "65") (name "unconnected-(IC1-NC_1-Pad28)") (class "Default")
      (node (ref "IC1") (pin "28") (pinfunction "NC_1_28") (pintype "passive+no_connect"))
    )
    (net (code "66") (name "unconnected-(IC1-NC_2-Pad29)") (class "Default")
      (node (ref "IC1") (pin "29") (pinfunction "NC_2_29") (pintype "passive+no_connect"))
    )
    (net (code "67") (name "unconnected-(IC1-NC_3-Pad30)") (class "Default")
      (node (ref "IC1") (pin "30") (pinfunction "NC_3_30") (pintype "passive+no_connect"))
    )
    (net (code "68") (name "unconnected-(IC2-ECG_N-Pad4)") (class "Default")
      (node (ref "IC2") (pin "4") (pinfunction "ECG_N_4") (pintype "passive+no_connect"))
    )
    (net (code "69") (name "unconnected-(IC2-ECG_P-Pad5)") (class "Default")
      (node (ref "IC2") (pin "5") (pinfunction "ECG_P_5") (pintype "passive+no_connect"))
    )
    (net (code "70") (name "unconnected-(IC2-NC_1-Pad1)") (class "Default")
      (node (ref "IC2") (pin "1") (pinfunction "NC_1_1") (pintype "passive+no_connect"))
    )
    (net (code "71") (name "unconnected-(IC2-NC_2-Pad2)") (class "Default")
      (node (ref "IC2") (pin "2") (pinfunction "NC_2_2") (pintype "passive+no_connect"))
    )
    (net (code "72") (name "unconnected-(IC2-NC_3-Pad3)") (class "Default")
      (node (ref "IC2") (pin "3") (pinfunction "NC_3_3") (pintype "passive+no_connect"))
    )
    (net (code "73") (name "unconnected-(IC2-NC_4-Pad6)") (class "Default")
      (node (ref "IC2") (pin "6") (pinfunction "NC_4_6") (pintype "passive+no_connect"))
    )
    (net (code "74") (name "unconnected-(IC2-NC_5-Pad10)") (class "Default")
      (node (ref "IC2") (pin "10") (pinfunction "NC_5_10") (pintype "passive+no_connect"))
    )
    (net (code "75") (name "unconnected-(IC2-NC_6-Pad11)") (class "Default")
      (node (ref "IC2") (pin "11") (pinfunction "NC_6_11") (pintype "passive+no_connect"))
    )
    (net (code "76") (name "unconnected-(IC2-NC_7-Pad12)") (class "Default")
      (node (ref "IC2") (pin "12") (pinfunction "NC_7_12") (pintype "passive+no_connect"))
    )
    (net (code "77") (name "unconnected-(IC2-NC_8-Pad22)") (class "Default")
      (node (ref "IC2") (pin "22") (pinfunction "NC_8_22") (pintype "passive+no_connect"))
    )
    (net (code "78") (name "unconnected-(IC3-CHR0-Pad15)") (class "Default")
      (node (ref "IC3") (pin "15") (pinfunction "CHR0_15") (pintype "output+no_connect"))
    )
    (net (code "79") (name "unconnected-(IC3-CHR1-Pad14)") (class "Default")
      (node (ref "IC3") (pin "14") (pinfunction "CHR1_14") (pintype "output+no_connect"))
    )
    (net (code "80") (name "unconnected-(IC3-CHREN-Pad13)") (class "Default")
      (node (ref "IC3") (pin "13") (pinfunction "CHREN_13") (pintype "output+no_connect"))
    )
    (net (code "81") (name "unconnected-(IC3-CTS-Pad23)") (class "Default")
      (node (ref "IC3") (pin "23") (pinfunction "CTS_23") (pintype "input+no_connect"))
    )
    (net (code "82") (name "unconnected-(IC3-DCD-Pad1)") (class "Default")
      (node (ref "IC3") (pin "1") (pinfunction "DCD_1") (pintype "input+no_connect"))
    )
    (net (code "83") (name "unconnected-(IC3-DSR-Pad27)") (class "Default")
      (node (ref "IC3") (pin "27") (pinfunction "DSR_27") (pintype "input+no_connect"))
    )
    (net (code "84") (name "unconnected-(IC3-GPIO.0{slash}TXT-Pad19)") (class "Default")
      (node (ref "IC3") (pin "19") (pinfunction "GPIO.0/TXT_19") (pintype "bidirectional+no_connect"))
    )
    (net (code "85") (name "unconnected-(IC3-GPIO.1{slash}RXT-Pad18)") (class "Default")
      (node (ref "IC3") (pin "18") (pinfunction "GPIO.1/RXT_18") (pintype "bidirectional+no_connect"))
    )
    (net (code "86") (name "unconnected-(IC3-GPIO.2{slash}RS485-Pad17)") (class "Default")
      (node (ref "IC3") (pin "17") (pinfunction "GPIO.2/RS485_17") (pintype "bidirectional+no_connect"))
    )
    (net (code "87") (name "unconnected-(IC3-GPIO.3{slash}WAKEUP-Pad16)") (class "Default")
      (node (ref "IC3") (pin "16") (pinfunction "GPIO.3/WAKEUP_16") (pintype "bidirectional+no_connect"))
    )
    (net (code "88") (name "unconnected-(IC3-GPIO.4-Pad22)") (class "Default")
      (node (ref "IC3") (pin "22") (pinfunction "GPIO.4_22") (pintype "bidirectional+no_connect"))
    )
    (net (code "89") (name "unconnected-(IC3-GPIO.5-Pad21)") (class "Default")
      (node (ref "IC3") (pin "21") (pinfunction "GPIO.5_21") (pintype "bidirectional+no_connect"))
    )
    (net (code "90") (name "unconnected-(IC3-GPIO.6-Pad20)") (class "Default")
      (node (ref "IC3") (pin "20") (pinfunction "GPIO.6_20") (pintype "bidirectional+no_connect"))
    )
    (net (code "91") (name "unconnected-(IC3-NC-Pad10)") (class "Default")
      (node (ref "IC3") (pin "10") (pinfunction "NC_10") (pintype "passive+no_connect"))
    )
    (net (code "92") (name "unconnected-(IC3-RI{slash}CLK-Pad2)") (class "Default")
      (node (ref "IC3") (pin "2") (pinfunction "RI/CLK_2") (pintype "bidirectional+no_connect"))
    )
    (net (code "93") (name "unconnected-(IC3-SUSPEND-Pad12)") (class "Default")
      (node (ref "IC3") (pin "12") (pinfunction "SUSPEND_12") (pintype "output+no_connect"))
    )
    (net (code "94") (name "unconnected-(IC4-ADJ{slash}NC-Pad4)") (class "Default")
      (node (ref "IC4") (pin "4") (pinfunction "ADJ/NC_4") (pintype "passive+no_connect"))
    )
    (net (code "95") (name "unconnected-(IC5-NC-Pad4)") (class "Default")
      (node (ref "IC5") (pin "4") (pinfunction "NC_4") (pintype "passive+no_connect"))
    )
    (net (code "96") (name "unconnected-(IC6-A4-Pad5)") (class "Default")
      (node (ref "IC6") (pin "5") (pinfunction "A4_5") (pintype "passive+no_connect"))
    )
    (net (code "97") (name "unconnected-(IC6-B4-Pad10)") (class "Default")
      (node (ref "IC6") (pin "10") (pinfunction "B4_10") (pintype "passive+no_connect"))
    )
    (net (code "98") (name "unconnected-(IC6-NC_1-Pad6)") (class "Default")
      (node (ref "IC6") (pin "6") (pinfunction "NC_1_6") (pintype "passive+no_connect"))
    )
    (net (code "99") (name "unconnected-(IC6-NC_2-Pad9)") (class "Default")
      (node (ref "IC6") (pin "9") (pinfunction "NC_2_9") (pintype "passive+no_connect"))
    )
    (net (code "100") (name "unconnected-(J1-Pad4)") (class "Default")
      (node (ref "J1") (pin "4") (pinfunction "4_4") (pintype "passive+no_connect"))
    )
    (net (code "101") (name "unconnected-(J2-PadMH1)") (class "Default")
      (node (ref "J2") (pin "MH1") (pinfunction "MH1_MH1") (pintype "passive+no_connect"))
    )
    (net (code "102") (name "unconnected-(J2-PadMH2)") (class "Default")
      (node (ref "J2") (pin "MH2") (pinfunction "MH2_MH2") (pintype "passive+no_connect"))
    )
    (net (code "103") (name "unconnected-(J2-PadMH3)") (class "Default")
      (node (ref "J2") (pin "MH3") (pinfunction "MH3_MH3") (pintype "passive+no_connect"))
    )
    (net (code "104") (name "unconnected-(J2-PadMH4)") (class "Default")
      (node (ref "J2") (pin "MH4") (pinfunction "MH4_MH4") (pintype "passive+no_connect"))
    )
    (net (code "105") (name "unconnected-(J3-MNT_1-Pad3)") (class "Default")
      (node (ref "J3") (pin "3") (pinfunction "MNT_1_3") (pintype "passive+no_connect"))
    )
    (net (code "106") (name "unconnected-(J3-MNT_2-Pad4)") (class "Default")
      (node (ref "J3") (pin "4") (pinfunction "MNT_2_4") (pintype "passive+no_connect"))
    )
    (net (code "107") (name "unconnected-(SW1-1'_-_NO-Pad3)") (class "Default")
      (node (ref "SW1") (pin "3") (pinfunction "1'_-_NO_3") (pintype "passive+no_connect"))
    )
    (net (code "108") (name "unconnected-(SW1-2_-_COM-Pad2)") (class "Default")
      (node (ref "SW1") (pin "2") (pinfunction "2_-_COM_2") (pintype "passive+no_connect"))
    )
    (net (code "109") (name "unconnected-(SW2-1'_-_NO-Pad3)") (class "Default")
      (node (ref "SW2") (pin "3") (pinfunction "1'_-_NO_3") (pintype "passive+no_connect"))
    )
    (net (code "110") (name "unconnected-(SW2-2_-_COM-Pad2)") (class "Default")
      (node (ref "SW2") (pin "2") (pinfunction "2_-_COM_2") (pintype "passive+no_connect"))
    )
  )
)
